# LIMITSWITCH_SCH.net
KiCad netlist of a schematic drawn in Altium Designer
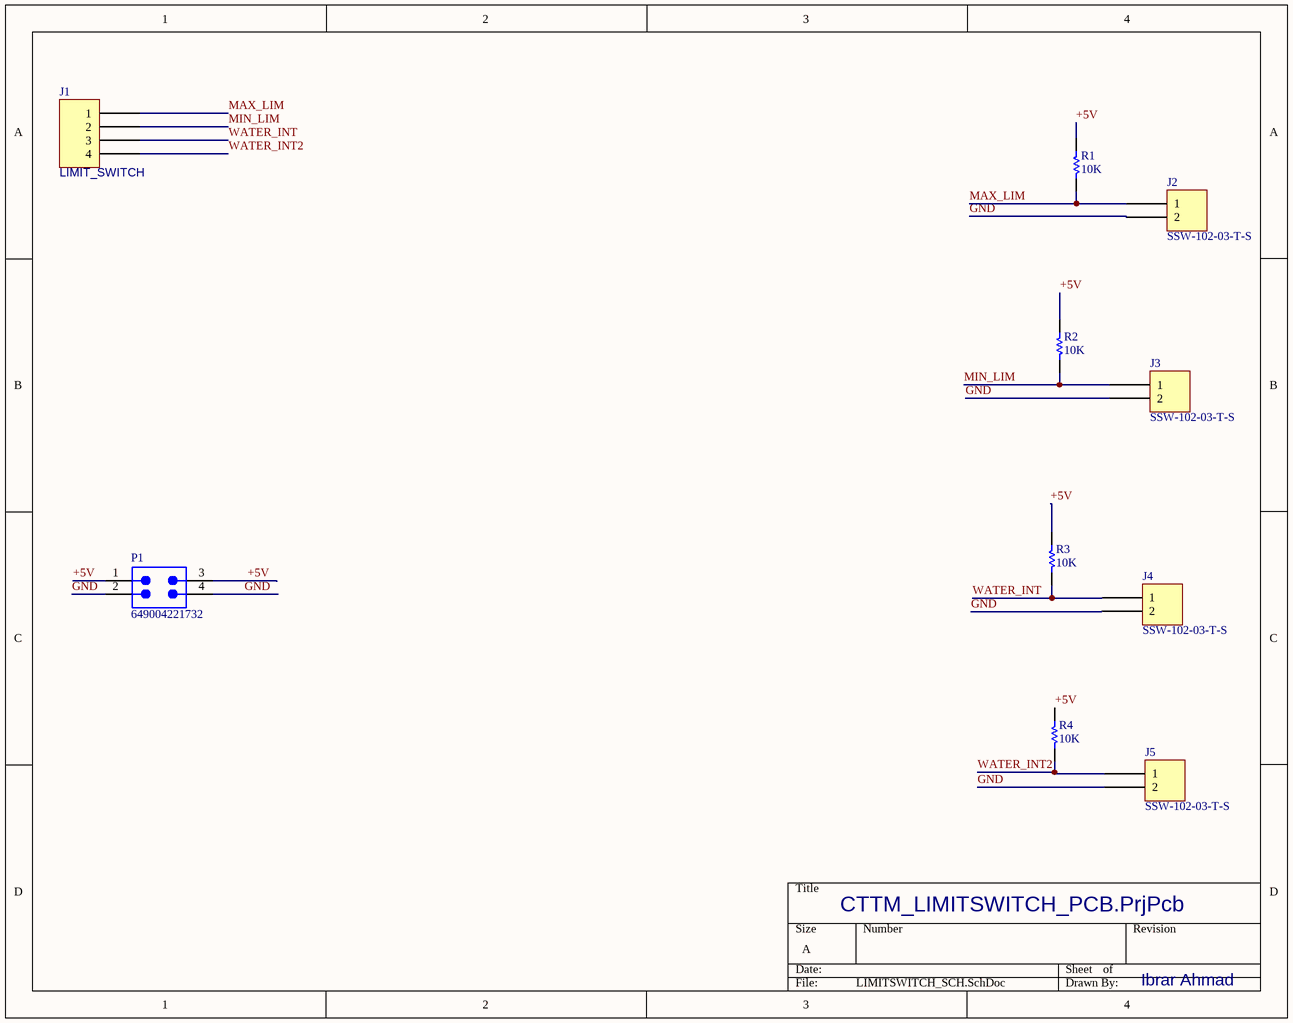
[diagram p0: LIMITSWITCH_SCH.SchDoc]

(export (version "E")
  (design (tool "Eeschema 10.0.6"))
  (components
    (comp (ref "J1")
      (value "LIMIT_SWITCH")
      (footprint "MOLEX 395021004")
      (description "TERM BLOCK HDR 4POS 90DEG 3.5MM")
      (fields (field (name "PART NUMBER") "0395021004") (field (name "MANUFACTURER") "Molex"))
      (libsource (lib "Celestial Altium Library - altium_library") (part "4 Pin"))
    )
    (comp (ref "J2")
      (value "SSW-102-03-T-S")
      (footprint "SAMTEC SSW-102-03-T-S")
      (description "CONN RCPT 2POS 0.1 TIN PCB")
      (fields (field (name "MANUFACTURER") "Samtec Inc."))
      (libsource (lib "Celestial Altium Library - altium_library") (part "2 Pin"))
    )
    (comp (ref "J3")
      (value "SSW-102-03-T-S")
      (footprint "SAMTEC SSW-102-03-T-S")
      (description "CONN RCPT 2POS 0.1 TIN PCB")
      (fields (field (name "MANUFACTURER") "Samtec Inc."))
      (libsource (lib "Celestial Altium Library - altium_library") (part "2 Pin"))
    )
    (comp (ref "J4")
      (value "SSW-102-03-T-S")
      (footprint "SAMTEC SSW-102-03-T-S")
      (description "CONN RCPT 2POS 0.1 TIN PCB")
      (fields (field (name "MANUFACTURER") "Samtec Inc."))
      (libsource (lib "Celestial Altium Library - altium_library") (part "2 Pin"))
    )
    (comp (ref "J5")
      (value "SSW-102-03-T-S")
      (footprint "SAMTEC SSW-102-03-T-S")
      (description "CONN RCPT 2POS 0.1 TIN PCB")
      (fields (field (name "MANUFACTURER") "Samtec Inc."))
      (libsource (lib "Celestial Altium Library - altium_library") (part "2 Pin"))
    )
    (comp (ref "P1")
      (value "649004221732")
      (footprint "649004221732")
      (libsource (lib "Altium Content Vault") (part "Header_Male_2R_04P(A)"))
    )
    (comp (ref "R1")
      (value "CRA06E08310K0JTA")
      (footprint "RESC3215X60X61NL15T15")
      (fields (field (name "MANUFACTURER") "Vishay Dale") (field (name "RESISTANCE") "10K"))
      (libsource (lib "Altium Content Vault") (part "RES"))
    )
    (comp (ref "R2")
      (value "CRA06E08310K0JTA")
      (footprint "RESC3215X60X61NL15T15")
      (fields (field (name "MANUFACTURER") "Vishay Dale") (field (name "RESISTANCE") "10K"))
      (libsource (lib "Altium Content Vault") (part "RES"))
    )
    (comp (ref "R3")
      (value "CRA06E08310K0JTA")
      (footprint "RESC3215X60X61NL15T15")
      (fields (field (name "MANUFACTURER") "Vishay Dale") (field (name "RESISTANCE") "10K"))
      (libsource (lib "Altium Content Vault") (part "RES"))
    )
    (comp (ref "R4")
      (value "CRA06E08310K0JTA")
      (footprint "RESC3215X60X61NL15T15")
      (fields (field (name "MANUFACTURER") "Vishay Dale") (field (name "RESISTANCE") "10K"))
      (libsource (lib "Altium Content Vault") (part "RES"))
    )
  )
  (nets
    (net (code "1") (name "/+5V") (class "Default")
      (node (ref "P1") (pin "1") (pinfunction "1_1") (pintype "passive"))
      (node (ref "P1") (pin "3") (pinfunction "3_3") (pintype "passive"))
      (node (ref "R1") (pin "2") (pinfunction "2_2") (pintype "passive"))
      (node (ref "R2") (pin "2") (pinfunction "2_2") (pintype "passive"))
      (node (ref "R3") (pin "2") (pinfunction "2_2") (pintype "passive"))
      (node (ref "R4") (pin "2") (pinfunction "2_2") (pintype "passive"))
    )
    (net (code "2") (name "/GND") (class "Default")
      (node (ref "J2") (pin "2") (pinfunction "2_2") (pintype "passive"))
      (node (ref "J3") (pin "2") (pinfunction "2_2") (pintype "passive"))
      (node (ref "J4") (pin "2") (pinfunction "2_2") (pintype "passive"))
      (node (ref "J5") (pin "2") (pinfunction "2_2") (pintype "passive"))
      (node (ref "P1") (pin "2") (pinfunction "2_2") (pintype "passive"))
      (node (ref "P1") (pin "4") (pinfunction "4_4") (pintype "passive"))
    )
    (net (code "3") (name "/MAX_LIM") (class "Default")
      (node (ref "J1") (pin "1") (pinfunction "1_1") (pintype "passive"))
      (node (ref "J2") (pin "1") (pinfunction "1_1") (pintype "passive"))
      (node (ref "R1") (pin "1") (pinfunction "1_1") (pintype "passive"))
    )
    (net (code "4") (name "/MIN_LIM") (class "Default")
      (node (ref "J1") (pin "2") (pinfunction "2_2") (pintype "passive"))
      (node (ref "J3") (pin "1") (pinfunction "1_1") (pintype "passive"))
      (node (ref "R2") (pin "1") (pinfunction "1_1") (pintype "passive"))
    )
    (net (code "5") (name "/WATER_INT") (class "Default")
      (node (ref "J1") (pin "3") (pinfunction "3_3") (pintype "passive"))
      (node (ref "J4") (pin "1") (pinfunction "1_1") (pintype "passive"))
      (node (ref "R3") (pin "1") (pinfunction "1_1") (pintype "passive"))
    )
    (net (code "6") (name "/WATER_INT2") (class "Default")
      (node (ref "J1") (pin "4") (pinfunction "4_4") (pintype "passive"))
      (node (ref "J5") (pin "1") (pinfunction "1_1") (pintype "passive"))
      (node (ref "R4") (pin "1") (pinfunction "1_1") (pintype "passive"))
    )
  )
)
